# Power_Management_Tester.net
KiCad netlist of a schematic drawn in EAGLE
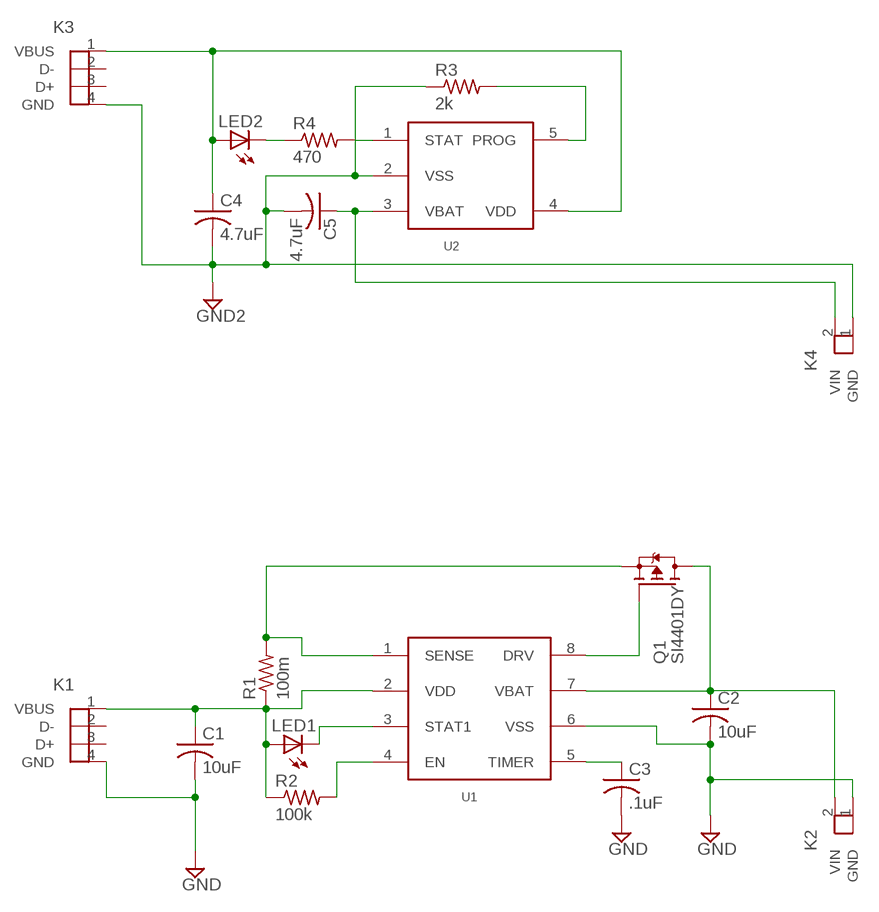
[diagram p0: schematic, sheet 1]

(export (version "E")
  (design (tool "Eeschema 10.0.6"))
  (components
    (comp (ref "C1")
      (value "10uF")
      (footprint "eagle-import:0805")
      (libsource (lib "eagle-import") (part "CAP0805"))
    )
    (comp (ref "C2")
      (value "10uF")
      (footprint "eagle-import:0805")
      (libsource (lib "eagle-import") (part "CAP0805"))
    )
    (comp (ref "C3")
      (value ".1uF")
      (footprint "eagle-import:0603")
      (libsource (lib "eagle-import") (part "CAP0603"))
    )
    (comp (ref "C4")
      (value "4.7uF")
      (footprint "eagle-import:0805")
      (libsource (lib "eagle-import") (part "CAP0805"))
    )
    (comp (ref "C5")
      (value "4.7uF")
      (footprint "eagle-import:0805")
      (libsource (lib "eagle-import") (part "CAP0805"))
    )
    (comp (ref "K1")
      (value "USBCONN")
      (footprint "eagle-import:USB_RECEPT(CNC)")
      (libsource (lib "eagle-import") (part "USBCONN"))
    )
    (comp (ref "K2")
      (value "PWRCONN")
      (footprint "eagle-import:2CONN")
      (libsource (lib "eagle-import") (part "PWRCONN"))
    )
    (comp (ref "K3")
      (value "USBCONN")
      (footprint "eagle-import:USB_RECEPT(CNC)")
      (libsource (lib "eagle-import") (part "USBCONN"))
    )
    (comp (ref "K4")
      (value "PWRCONN")
      (footprint "eagle-import:2CONN")
      (libsource (lib "eagle-import") (part "PWRCONN"))
    )
    (comp (ref "LED1")
      (value "LED0805")
      (footprint "eagle-import:0805")
      (libsource (lib "eagle-import") (part "LED0805"))
    )
    (comp (ref "LED2")
      (value "LED0805")
      (footprint "eagle-import:0805")
      (libsource (lib "eagle-import") (part "LED0805"))
    )
    (comp (ref "Q1")
      (value "SI4401DY")
      (footprint "eagle-import:8-SOIC")
      (libsource (lib "eagle-import") (part "SI4401DY"))
    )
    (comp (ref "R1")
      (value "100m")
      (footprint "eagle-import:0805")
      (libsource (lib "eagle-import") (part "R0805"))
    )
    (comp (ref "R2")
      (value "100k")
      (footprint "eagle-import:0603")
      (libsource (lib "eagle-import") (part "R0603"))
    )
    (comp (ref "R3")
      (value "2k")
      (footprint "eagle-import:0603")
      (libsource (lib "eagle-import") (part "R0603"))
    )
    (comp (ref "R4")
      (value "470")
      (footprint "eagle-import:0603")
      (libsource (lib "eagle-import") (part "R0603"))
    )
    (comp (ref "U1")
      (value "MCP73843")
      (footprint "eagle-import:8-MSOP")
      (libsource (lib "eagle-import") (part "MCP73843"))
    )
    (comp (ref "U2")
      (value "MCP73831")
      (footprint "eagle-import:SOT-23")
      (libsource (lib "eagle-import") (part "MCP73831"))
    )
  )
  (nets
    (net (code "1") (name "GND") (class "Default")
      (node (ref "C1") (pin "A1") (pinfunction "2_A1") (pintype "passive"))
      (node (ref "C2") (pin "A1") (pinfunction "2_A1") (pintype "passive"))
      (node (ref "C3") (pin "2") (pinfunction "2_2") (pintype "passive"))
      (node (ref "K1") (pin "4") (pinfunction "GND_4") (pintype "bidirectional"))
      (node (ref "K2") (pin "1") (pinfunction "GND_1") (pintype "bidirectional"))
      (node (ref "U1") (pin "6") (pinfunction "VSS_6") (pintype "bidirectional"))
    )
    (net (code "2") (name "GND2") (class "Default")
      (node (ref "C4") (pin "A1") (pinfunction "2_A1") (pintype "passive"))
      (node (ref "C5") (pin "A1") (pinfunction "2_A1") (pintype "passive"))
      (node (ref "K3") (pin "4") (pinfunction "GND_4") (pintype "bidirectional"))
      (node (ref "K4") (pin "1") (pinfunction "GND_1") (pintype "bidirectional"))
      (node (ref "R3") (pin "1") (pinfunction "1_1") (pintype "passive"))
      (node (ref "U2") (pin "2") (pinfunction "VSS_2") (pintype "bidirectional"))
    )
    (net (code "3") (name "Net-(C1-1)") (class "Default")
      (node (ref "C1") (pin "A") (pinfunction "1_A") (pintype "passive"))
      (node (ref "K1") (pin "1") (pinfunction "VBUS_1") (pintype "bidirectional"))
      (node (ref "LED1") (pin "A") (pinfunction "POS_A") (pintype "passive"))
      (node (ref "R1") (pin "A") (pinfunction "1_A") (pintype "passive"))
      (node (ref "R2") (pin "1") (pinfunction "1_1") (pintype "passive"))
      (node (ref "U1") (pin "2") (pinfunction "VDD_2") (pintype "bidirectional"))
    )
    (net (code "4") (name "Net-(C2-1)") (class "Default")
      (node (ref "C2") (pin "A") (pinfunction "1_A") (pintype "passive"))
      (node (ref "K2") (pin "2") (pinfunction "VIN_2") (pintype "bidirectional"))
      (node (ref "Q1") (pin "5") (pinfunction "D_5") (pintype "passive"))
      (node (ref "Q1") (pin "6") (pinfunction "D_6") (pintype "passive"))
      (node (ref "Q1") (pin "7") (pinfunction "D_7") (pintype "passive"))
      (node (ref "Q1") (pin "8") (pinfunction "D_8") (pintype "passive"))
      (node (ref "U1") (pin "7") (pinfunction "VBAT_7") (pintype "bidirectional"))
    )
    (net (code "5") (name "Net-(C4-1)") (class "Default")
      (node (ref "C4") (pin "A") (pinfunction "1_A") (pintype "passive"))
      (node (ref "K3") (pin "1") (pinfunction "VBUS_1") (pintype "bidirectional"))
      (node (ref "LED2") (pin "A") (pinfunction "POS_A") (pintype "passive"))
      (node (ref "U2") (pin "4") (pinfunction "VDD_4") (pintype "bidirectional"))
    )
    (net (code "6") (name "Net-(C5-1)") (class "Default")
      (node (ref "C5") (pin "A") (pinfunction "1_A") (pintype "passive"))
      (node (ref "K4") (pin "2") (pinfunction "VIN_2") (pintype "bidirectional"))
      (node (ref "U2") (pin "3") (pinfunction "VBAT_3") (pintype "bidirectional"))
    )
    (net (code "7") (name "Net-(LED1-NEG)") (class "Default")
      (node (ref "LED1") (pin "A1") (pinfunction "NEG_A1") (pintype "passive"))
      (node (ref "U1") (pin "3") (pinfunction "STAT1_3") (pintype "bidirectional"))
    )
    (net (code "8") (name "Net-(LED2-NEG)") (class "Default")
      (node (ref "LED2") (pin "A1") (pinfunction "NEG_A1") (pintype "passive"))
      (node (ref "R4") (pin "1") (pinfunction "1_1") (pintype "passive"))
    )
    (net (code "9") (name "Net-(Q1-G)") (class "Default")
      (node (ref "Q1") (pin "4") (pinfunction "G_4") (pintype "passive"))
      (node (ref "U1") (pin "8") (pinfunction "DRV_8") (pintype "bidirectional"))
    )
    (net (code "10") (name "Net-(R1-2)") (class "Default")
      (node (ref "Q1") (pin "1") (pinfunction "S_1") (pintype "passive"))
      (node (ref "Q1") (pin "2") (pinfunction "S_2") (pintype "passive"))
      (node (ref "Q1") (pin "3") (pinfunction "S_3") (pintype "passive"))
      (node (ref "R1") (pin "A1") (pinfunction "2_A1") (pintype "passive"))
      (node (ref "U1") (pin "1") (pinfunction "SENSE_1") (pintype "bidirectional"))
    )
    (net (code "11") (name "Net-(U1-EN)") (class "Default")
      (node (ref "R2") (pin "2") (pinfunction "2_2") (pintype "passive"))
      (node (ref "U1") (pin "4") (pinfunction "EN_4") (pintype "bidirectional"))
    )
    (net (code "12") (name "Net-(U1-TIMER)") (class "Default")
      (node (ref "C3") (pin "1") (pinfunction "1_1") (pintype "passive"))
      (node (ref "U1") (pin "5") (pinfunction "TIMER_5") (pintype "bidirectional"))
    )
    (net (code "13") (name "Net-(U2-PROG)") (class "Default")
      (node (ref "R3") (pin "2") (pinfunction "2_2") (pintype "passive"))
      (node (ref "U2") (pin "5") (pinfunction "PROG_5") (pintype "bidirectional"))
    )
    (net (code "14") (name "Net-(U2-STAT)") (class "Default")
      (node (ref "R4") (pin "2") (pinfunction "2_2") (pintype "passive"))
      (node (ref "U2") (pin "1") (pinfunction "STAT_1") (pintype "bidirectional"))
    )
    (net (code "15") (name "unconnected-(K1-D+-Pad3)") (class "Default")
      (node (ref "K1") (pin "3") (pinfunction "D+_3") (pintype "bidirectional"))
    )
    (net (code "16") (name "unconnected-(K1-D--Pad2)") (class "Default")
      (node (ref "K1") (pin "2") (pinfunction "D-_2") (pintype "bidirectional"))
    )
    (net (code "17") (name "unconnected-(K3-D+-Pad3)") (class "Default")
      (node (ref "K3") (pin "3") (pinfunction "D+_3") (pintype "bidirectional"))
    )
    (net (code "18") (name "unconnected-(K3-D--Pad2)") (class "Default")
      (node (ref "K3") (pin "2") (pinfunction "D-_2") (pintype "bidirectional"))
    )
  )
)
